# sheet1.net
KiCad netlist of a schematic drawn in Altium Designer
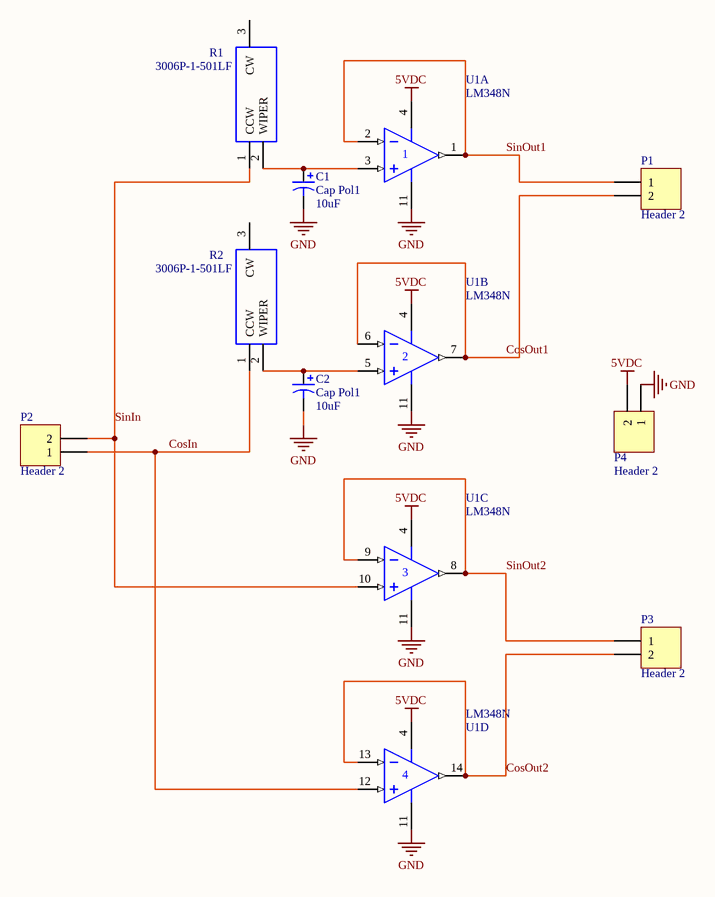
[diagram p0: sheet1.SchDoc]

(export (version "E")
  (design (tool "Eeschema 10.0.6"))
  (components
    (comp (ref "C1")
      (value "Cap Pol1")
      (footprint "AXIAL-0.4")
      (description "Polarized Capacitor (Radial)")
      (fields (field (name "ALTIUM_VALUE") "10uF") (field (name "PUBLISHER") "Altium Limited"))
      (libsource (lib "Miscellaneous Devices") (part "Cap Pol1"))
    )
    (comp (ref "C2")
      (value "Cap Pol1")
      (footprint "AXIAL-0.4")
      (description "Polarized Capacitor (Radial)")
      (fields (field (name "ALTIUM_VALUE") "10uF") (field (name "PUBLISHER") "Altium Limited"))
      (libsource (lib "Miscellaneous Devices") (part "Cap Pol1"))
    )
    (comp (ref "P1")
      (value "Header 2")
      (footprint "HDR1X2")
      (description "Header, 2-Pin")
      (fields (field (name "PUBLISHER") "Altium Limited"))
      (libsource (lib "") (part "Header 2_1"))
    )
    (comp (ref "P2")
      (value "Header 2")
      (footprint "HDR1X2")
      (description "Header, 2-Pin")
      (fields (field (name "PUBLISHER") "Altium Limited"))
      (libsource (lib "") (part "Header 2_2"))
    )
    (comp (ref "P3")
      (value "Header 2")
      (footprint "HDR1X2")
      (description "Header, 2-Pin")
      (fields (field (name "PUBLISHER") "Altium Limited"))
      (libsource (lib "") (part "Header 2_1"))
    )
    (comp (ref "P4")
      (value "Header 2")
      (footprint "HDR1X2")
      (description "Header, 2-Pin")
      (fields (field (name "PUBLISHER") "Altium Limited"))
      (libsource (lib "Miscellaneous Connectors") (part "Header 2"))
    )
    (comp (ref "R1")
      (value "3006P-1-501LF")
      (footprint "3006P_1")
      (description "BOURNS - 3006P-1-501LF - TRIMMER, 15 TURN 500R")
      (fields
        (field (name "RS PART NUMBER") "5219120")
        (field (name "MOUSER PART NUMBER") "652-3006P-1-501-LF")
      )
      (libsource (lib "3006P-1-501LF") (part "3006P-1-501LF"))
    )
    (comp (ref "R2")
      (value "3006P-1-501LF")
      (footprint "3006P_1")
      (description "BOURNS - 3006P-1-501LF - TRIMMER, 15 TURN 500R")
      (fields
        (field (name "RS PART NUMBER") "5219120")
        (field (name "MOUSER PART NUMBER") "652-3006P-1-501-LF")
      )
      (libsource (lib "3006P-1-501LF") (part "3006P-1-501LF"))
    )
    (comp (ref "U1")
      (value "LM348N")
      (footprint "646-06")
      (description "Quad General-Purpose Operational Amplifier")
      (fields (field (name "PUBLISHER") "Altium Limited"))
      (libsource (lib "Motorola Amplifier Operational Amplifier") (part "LM348N"))
    )
  )
  (nets
    (net (code "1") (name "/CosIn") (class "Default")
      (node (ref "P2") (pin "1") (pinfunction "1_1") (pintype "passive"))
      (node (ref "R2") (pin "1") (pinfunction "CCW_1") (pintype "passive"))
      (node (ref "U1") (pin "12") (pinfunction "IN+_12") (pintype "input"))
    )
    (net (code "2") (name "/CosOut1") (class "Default")
      (node (ref "P1") (pin "2") (pinfunction "2_2") (pintype "passive"))
      (node (ref "U1") (pin "6") (pinfunction "IN-_6") (pintype "input"))
      (node (ref "U1") (pin "7") (pinfunction "OUT_7") (pintype "output"))
    )
    (net (code "3") (name "/CosOut2") (class "Default")
      (node (ref "P3") (pin "2") (pinfunction "2_2") (pintype "passive"))
      (node (ref "U1") (pin "13") (pinfunction "IN-_13") (pintype "input"))
      (node (ref "U1") (pin "14") (pinfunction "OUT_14") (pintype "output"))
    )
    (net (code "4") (name "/SinIn") (class "Default")
      (node (ref "P2") (pin "2") (pinfunction "2_2") (pintype "passive"))
      (node (ref "R1") (pin "1") (pinfunction "CCW_1") (pintype "passive"))
      (node (ref "U1") (pin "10") (pinfunction "IN+_10") (pintype "input"))
    )
    (net (code "5") (name "/SinOut1") (class "Default")
      (node (ref "P1") (pin "1") (pinfunction "1_1") (pintype "passive"))
      (node (ref "U1") (pin "1") (pinfunction "OUT_1") (pintype "output"))
      (node (ref "U1") (pin "2") (pinfunction "IN-_2") (pintype "input"))
    )
    (net (code "6") (name "/SinOut2") (class "Default")
      (node (ref "P3") (pin "1") (pinfunction "1_1") (pintype "passive"))
      (node (ref "U1") (pin "8") (pinfunction "OUT_8") (pintype "output"))
      (node (ref "U1") (pin "9") (pinfunction "IN-_9") (pintype "input"))
    )
    (net (code "7") (name "5VDC") (class "Default")
      (node (ref "P4") (pin "2") (pinfunction "2_2") (pintype "passive"))
      (node (ref "U1") (pin "4") (pinfunction "V+_4") (pintype "power_in"))
    )
    (net (code "8") (name "GND") (class "Default")
      (node (ref "C1") (pin "2") (pinfunction "2_2") (pintype "passive"))
      (node (ref "C2") (pin "2") (pinfunction "2_2") (pintype "passive"))
      (node (ref "P4") (pin "1") (pinfunction "1_1") (pintype "passive"))
      (node (ref "U1") (pin "11") (pinfunction "V-_11") (pintype "power_in"))
    )
    (net (code "9") (name "Net-(R1-WIPER)") (class "Default")
      (node (ref "C1") (pin "1") (pinfunction "1_1") (pintype "passive"))
      (node (ref "R1") (pin "2") (pinfunction "WIPER_2") (pintype "passive"))
      (node (ref "U1") (pin "3") (pinfunction "IN+_3") (pintype "input"))
    )
    (net (code "10") (name "Net-(R2-WIPER)") (class "Default")
      (node (ref "C2") (pin "1") (pinfunction "1_1") (pintype "passive"))
      (node (ref "R2") (pin "2") (pinfunction "WIPER_2") (pintype "passive"))
      (node (ref "U1") (pin "5") (pinfunction "IN+_5") (pintype "input"))
    )
    (net (code "11") (name "unconnected-(R1-CW-Pad3)") (class "Default")
      (node (ref "R1") (pin "3") (pinfunction "CW_3") (pintype "passive"))
    )
    (net (code "12") (name "unconnected-(R2-CW-Pad3)") (class "Default")
      (node (ref "R2") (pin "3") (pinfunction "CW_3") (pintype "passive"))
    )
  )
)
